# Relay_schematic.net
KiCad netlist of a schematic drawn in Altium Designer
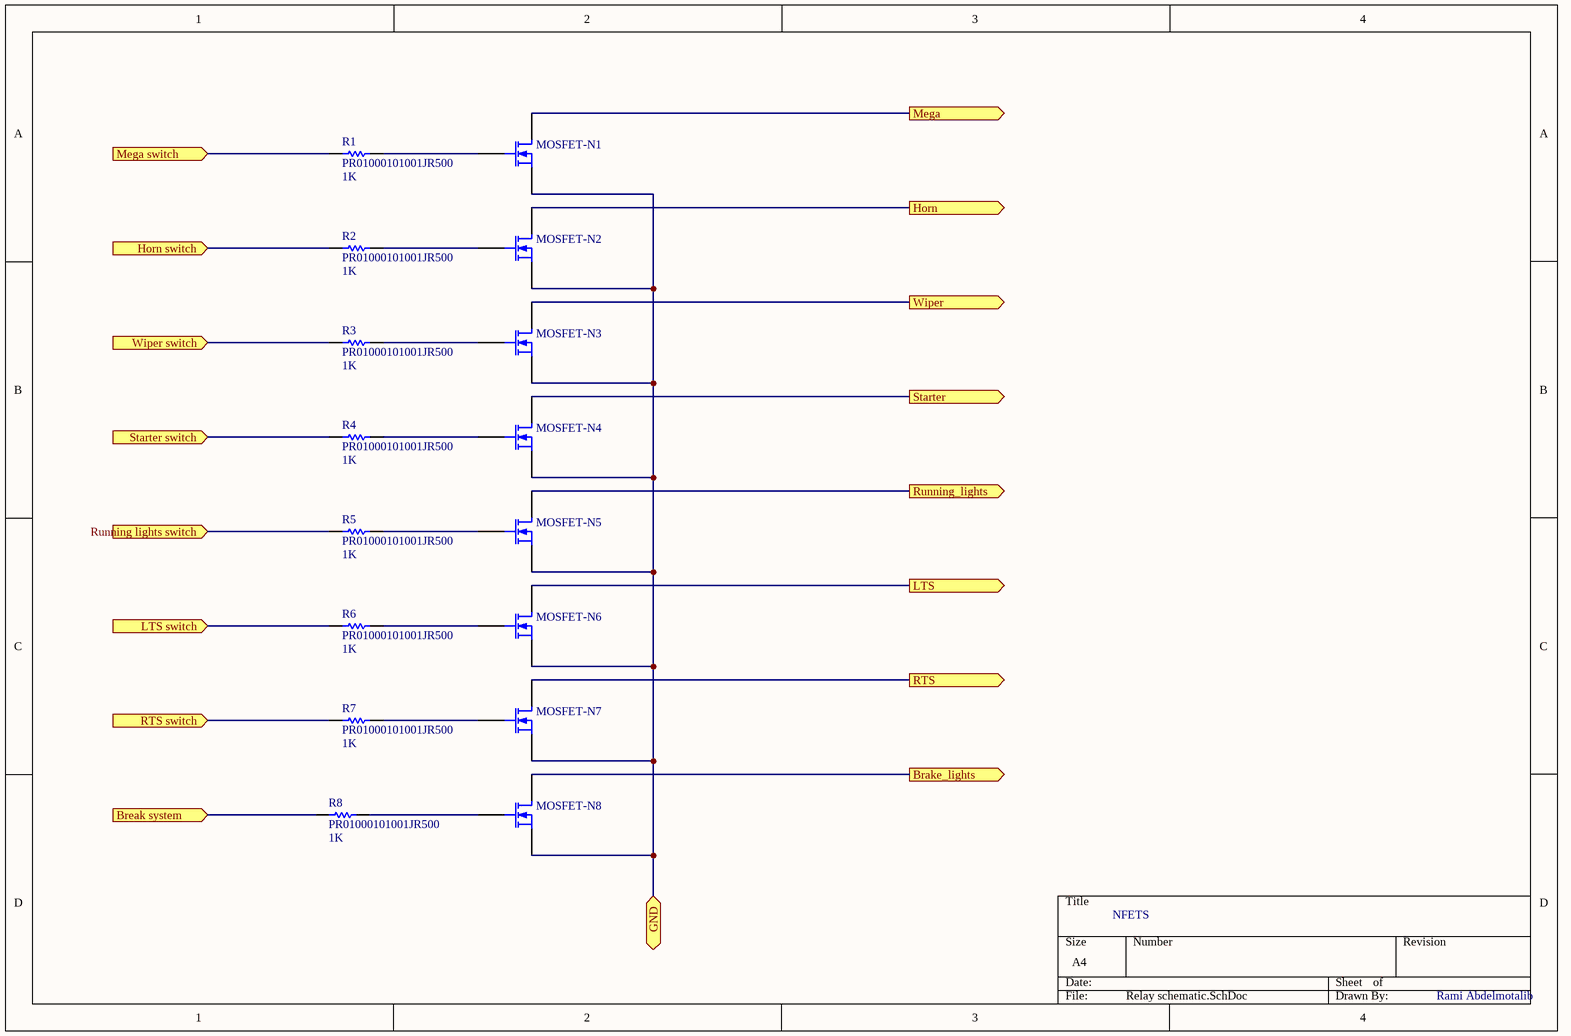
[diagram p0: Relay schematic.SchDoc]

(export (version "E")
  (design (tool "Eeschema 10.0.6"))
  (components
    (comp (ref "MOSFET-N1")
      (value "~")
      (footprint "D2pakMOSFET")
      (description "N-Channel MOSFET")
      (fields (field (name "PUBLISHER") "Altium Limited"))
      (libsource (lib "Miscellaneous Devices") (part "MOSFET-N"))
    )
    (comp (ref "MOSFET-N2")
      (value "~")
      (footprint "D2pakMOSFET")
      (description "N-Channel MOSFET")
      (fields (field (name "PUBLISHER") "Altium Limited"))
      (libsource (lib "Miscellaneous Devices") (part "MOSFET-N"))
    )
    (comp (ref "MOSFET-N3")
      (value "~")
      (footprint "D2pakMOSFET")
      (description "N-Channel MOSFET")
      (fields (field (name "PUBLISHER") "Altium Limited"))
      (libsource (lib "Miscellaneous Devices") (part "MOSFET-N"))
    )
    (comp (ref "MOSFET-N4")
      (value "~")
      (footprint "D2pakMOSFET")
      (description "N-Channel MOSFET")
      (fields (field (name "PUBLISHER") "Altium Limited"))
      (libsource (lib "Miscellaneous Devices") (part "MOSFET-N"))
    )
    (comp (ref "MOSFET-N5")
      (value "~")
      (footprint "D2pakMOSFET")
      (description "N-Channel MOSFET")
      (fields (field (name "PUBLISHER") "Altium Limited"))
      (libsource (lib "Miscellaneous Devices") (part "MOSFET-N"))
    )
    (comp (ref "MOSFET-N6")
      (value "~")
      (footprint "D2pakMOSFET")
      (description "N-Channel MOSFET")
      (fields (field (name "PUBLISHER") "Altium Limited"))
      (libsource (lib "Miscellaneous Devices") (part "MOSFET-N"))
    )
    (comp (ref "MOSFET-N7")
      (value "~")
      (footprint "D2pakMOSFET")
      (description "N-Channel MOSFET")
      (fields (field (name "PUBLISHER") "Altium Limited"))
      (libsource (lib "Miscellaneous Devices") (part "MOSFET-N"))
    )
    (comp (ref "MOSFET-N8")
      (value "~")
      (footprint "D2pakMOSFET")
      (description "N-Channel MOSFET")
      (fields (field (name "PUBLISHER") "Altium Limited"))
      (libsource (lib "Miscellaneous Devices") (part "MOSFET-N"))
    )
    (comp (ref "R1")
      (value "PR01000101001JR500")
      (footprint "AXIAL-0.3")
      (description "Resistor")
      (fields (field (name "ALTIUM_VALUE") "1K") (field (name "PUBLISHER") "Altium Limited"))
      (libsource (lib "Miscellaneous Devices") (part "Res1"))
    )
    (comp (ref "R2")
      (value "PR01000101001JR500")
      (footprint "AXIAL-0.3")
      (description "Resistor")
      (fields (field (name "ALTIUM_VALUE") "1K") (field (name "PUBLISHER") "Altium Limited"))
      (libsource (lib "Miscellaneous Devices") (part "Res1"))
    )
    (comp (ref "R3")
      (value "PR01000101001JR500")
      (footprint "AXIAL-0.3")
      (description "Resistor")
      (fields (field (name "ALTIUM_VALUE") "1K") (field (name "PUBLISHER") "Altium Limited"))
      (libsource (lib "Miscellaneous Devices") (part "Res1"))
    )
    (comp (ref "R4")
      (value "PR01000101001JR500")
      (footprint "AXIAL-0.3")
      (description "Resistor")
      (fields (field (name "ALTIUM_VALUE") "1K") (field (name "PUBLISHER") "Altium Limited"))
      (libsource (lib "Miscellaneous Devices") (part "Res1"))
    )
    (comp (ref "R5")
      (value "PR01000101001JR500")
      (footprint "AXIAL-0.3")
      (description "Resistor")
      (fields (field (name "ALTIUM_VALUE") "1K") (field (name "PUBLISHER") "Altium Limited"))
      (libsource (lib "Miscellaneous Devices") (part "Res1"))
    )
    (comp (ref "R6")
      (value "PR01000101001JR500")
      (footprint "AXIAL-0.3")
      (description "Resistor")
      (fields (field (name "ALTIUM_VALUE") "1K") (field (name "PUBLISHER") "Altium Limited"))
      (libsource (lib "Miscellaneous Devices") (part "Res1"))
    )
    (comp (ref "R7")
      (value "PR01000101001JR500")
      (footprint "AXIAL-0.3")
      (description "Resistor")
      (fields (field (name "ALTIUM_VALUE") "1K") (field (name "PUBLISHER") "Altium Limited"))
      (libsource (lib "Miscellaneous Devices") (part "Res1"))
    )
    (comp (ref "R8")
      (value "PR01000101001JR500")
      (footprint "AXIAL-0.3")
      (description "Resistor")
      (fields (field (name "ALTIUM_VALUE") "1K") (field (name "PUBLISHER") "Altium Limited"))
      (libsource (lib "Miscellaneous Devices") (part "Res1"))
    )
  )
  (nets
    (net (code "1") (name "/Brake_lights") (class "Default")
      (node (ref "MOSFET-N8") (pin "1") (pinfunction "D_1") (pintype "passive"))
    )
    (net (code "2") (name "/Break system") (class "Default")
      (node (ref "R8") (pin "1") (pinfunction "1_1") (pintype "passive"))
    )
    (net (code "3") (name "/GND") (class "Default")
      (node (ref "MOSFET-N1") (pin "3") (pinfunction "S_3") (pintype "passive"))
      (node (ref "MOSFET-N2") (pin "3") (pinfunction "S_3") (pintype "passive"))
      (node (ref "MOSFET-N3") (pin "3") (pinfunction "S_3") (pintype "passive"))
      (node (ref "MOSFET-N4") (pin "3") (pinfunction "S_3") (pintype "passive"))
      (node (ref "MOSFET-N5") (pin "3") (pinfunction "S_3") (pintype "passive"))
      (node (ref "MOSFET-N6") (pin "3") (pinfunction "S_3") (pintype "passive"))
      (node (ref "MOSFET-N7") (pin "3") (pinfunction "S_3") (pintype "passive"))
      (node (ref "MOSFET-N8") (pin "3") (pinfunction "S_3") (pintype "passive"))
    )
    (net (code "4") (name "/Horn") (class "Default")
      (node (ref "MOSFET-N2") (pin "1") (pinfunction "D_1") (pintype "passive"))
    )
    (net (code "5") (name "/Horn switch") (class "Default")
      (node (ref "R2") (pin "1") (pinfunction "1_1") (pintype "passive"))
    )
    (net (code "6") (name "/LTS") (class "Default")
      (node (ref "MOSFET-N6") (pin "1") (pinfunction "D_1") (pintype "passive"))
    )
    (net (code "7") (name "/LTS switch") (class "Default")
      (node (ref "R6") (pin "1") (pinfunction "1_1") (pintype "passive"))
    )
    (net (code "8") (name "/Mega") (class "Default")
      (node (ref "MOSFET-N1") (pin "1") (pinfunction "D_1") (pintype "passive"))
    )
    (net (code "9") (name "/Mega switch") (class "Default")
      (node (ref "R1") (pin "1") (pinfunction "1_1") (pintype "passive"))
    )
    (net (code "10") (name "/RTS") (class "Default")
      (node (ref "MOSFET-N7") (pin "1") (pinfunction "D_1") (pintype "passive"))
    )
    (net (code "11") (name "/RTS switch") (class "Default")
      (node (ref "R7") (pin "1") (pinfunction "1_1") (pintype "passive"))
    )
    (net (code "12") (name "/Running lights switch") (class "Default")
      (node (ref "R5") (pin "1") (pinfunction "1_1") (pintype "passive"))
    )
    (net (code "13") (name "/Running_lights") (class "Default")
      (node (ref "MOSFET-N5") (pin "1") (pinfunction "D_1") (pintype "passive"))
    )
    (net (code "14") (name "/Starter") (class "Default")
      (node (ref "MOSFET-N4") (pin "1") (pinfunction "D_1") (pintype "passive"))
    )
    (net (code "15") (name "/Starter switch") (class "Default")
      (node (ref "R4") (pin "1") (pinfunction "1_1") (pintype "passive"))
    )
    (net (code "16") (name "/Wiper") (class "Default")
      (node (ref "MOSFET-N3") (pin "1") (pinfunction "D_1") (pintype "passive"))
    )
    (net (code "17") (name "/Wiper switch") (class "Default")
      (node (ref "R3") (pin "1") (pinfunction "1_1") (pintype "passive"))
    )
    (net (code "18") (name "Net-(MOSFET-N1-G)") (class "Default")
      (node (ref "MOSFET-N1") (pin "2") (pinfunction "G_2") (pintype "passive"))
      (node (ref "R1") (pin "2") (pinfunction "2_2") (pintype "passive"))
    )
    (net (code "19") (name "Net-(MOSFET-N2-G)") (class "Default")
      (node (ref "MOSFET-N2") (pin "2") (pinfunction "G_2") (pintype "passive"))
      (node (ref "R2") (pin "2") (pinfunction "2_2") (pintype "passive"))
    )
    (net (code "20") (name "Net-(MOSFET-N3-G)") (class "Default")
      (node (ref "MOSFET-N3") (pin "2") (pinfunction "G_2") (pintype "passive"))
      (node (ref "R3") (pin "2") (pinfunction "2_2") (pintype "passive"))
    )
    (net (code "21") (name "Net-(MOSFET-N4-G)") (class "Default")
      (node (ref "MOSFET-N4") (pin "2") (pinfunction "G_2") (pintype "passive"))
      (node (ref "R4") (pin "2") (pinfunction "2_2") (pintype "passive"))
    )
    (net (code "22") (name "Net-(MOSFET-N5-G)") (class "Default")
      (node (ref "MOSFET-N5") (pin "2") (pinfunction "G_2") (pintype "passive"))
      (node (ref "R5") (pin "2") (pinfunction "2_2") (pintype "passive"))
    )
    (net (code "23") (name "Net-(MOSFET-N6-G)") (class "Default")
      (node (ref "MOSFET-N6") (pin "2") (pinfunction "G_2") (pintype "passive"))
      (node (ref "R6") (pin "2") (pinfunction "2_2") (pintype "passive"))
    )
    (net (code "24") (name "Net-(MOSFET-N7-G)") (class "Default")
      (node (ref "MOSFET-N7") (pin "2") (pinfunction "G_2") (pintype "passive"))
      (node (ref "R7") (pin "2") (pinfunction "2_2") (pintype "passive"))
    )
    (net (code "25") (name "Net-(MOSFET-N8-G)") (class "Default")
      (node (ref "MOSFET-N8") (pin "2") (pinfunction "G_2") (pintype "passive"))
      (node (ref "R8") (pin "2") (pinfunction "2_2") (pintype "passive"))
    )
  )
)
